# Sensor.net
KiCad netlist of a schematic drawn in Altium Designer
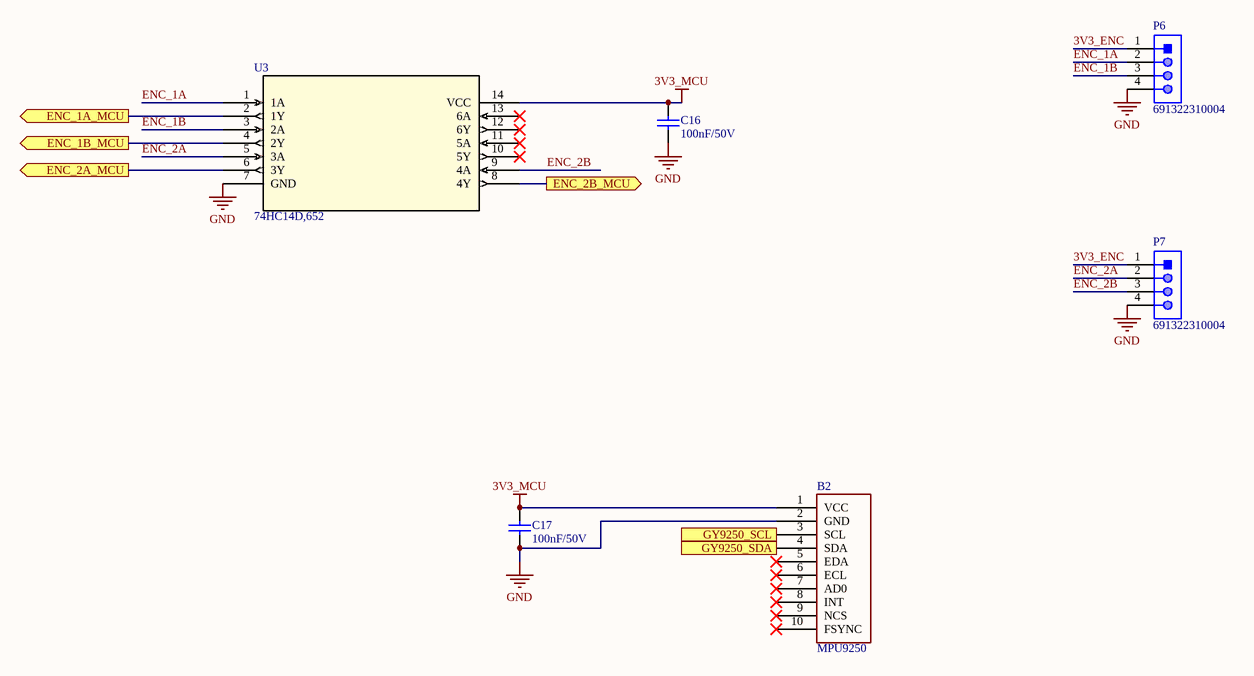
[diagram p0: Sensor.SchDoc]

(export (version "E")
  (design (tool "Eeschema 10.0.6"))
  (components
    (comp (ref "B2") (value "MPU9250") (footprint "MPU9250") (libsource (lib "Board") (part "MPU9250")))
    (comp (ref "C16")
      (value "100nF/50V")
      (footprint "CAP-SM-0805")
      (description "CAP CER 0.1UF 50V Y5V 0805")
      (fields
        (field (name "MANUFACTURER") "Samsung Electro-Mechanics")
        (field (name "MANUFACTURER PART NUMBER") "CL21F104ZBCNNNC")
      )
      (libsource (lib "Capacitor") (part "Cap-100nF-50V-0805"))
    )
    (comp (ref "C17")
      (value "100nF/50V")
      (footprint "CAP-SM-0805")
      (description "CAP CER 0.1UF 50V Y5V 0805")
      (fields
        (field (name "MANUFACTURER") "Samsung Electro-Mechanics")
        (field (name "MANUFACTURER PART NUMBER") "CL21F104ZBCNNNC")
      )
      (libsource (lib "Capacitor") (part "Cap-100nF-50V-0805"))
    )
    (comp (ref "P6")
      (value "691322310004")
      (footprint "Project_Xe_Can_Bang:691322310004")
      (description "WR-TBL Serie 322 Horizontal PCB Header, Pluggable, pitch 3.81mm, 4p")
      (fields (field (name "PUBLISHER") "Wurth Elektronik"))
      (libsource (lib "Project_Xe_Can_Bang") (part "691322310004"))
    )
    (comp (ref "P7")
      (value "691322310004")
      (footprint "Project_Xe_Can_Bang:691322310004")
      (description "WR-TBL Serie 322 Horizontal PCB Header, Pluggable, pitch 3.81mm, 4p")
      (fields (field (name "PUBLISHER") "Wurth Elektronik"))
      (libsource (lib "Project_Xe_Can_Bang") (part "691322310004"))
    )
    (comp (ref "U3")
      (value "74HC14D,652")
      (footprint "SOT108-1_NEX")
      (description "No Description Available")
      (fields (field (name "COPYRIGHT") "Copyright (C) 2016 Accelerated Designs. All rights reserved"))
      (libsource (lib "74HC14D_625_2020-06-19_15-46-23") (part "74HC14D,652"))
    )
  )
  (nets
    (net (code "1") (name "/3V3_ENC") (class "Default")
      (node (ref "P6") (pin "1") (pinfunction "1_1") (pintype "passive"))
      (node (ref "P7") (pin "1") (pinfunction "1_1") (pintype "passive"))
    )
    (net (code "2") (name "/ENC_1A") (class "Default")
      (node (ref "P6") (pin "2") (pinfunction "2_2") (pintype "passive"))
      (node (ref "U3") (pin "1") (pinfunction "1A_1") (pintype "input"))
    )
    (net (code "3") (name "/ENC_1A_MCU") (class "Default")
      (node (ref "U3") (pin "2") (pinfunction "1Y_2") (pintype "output"))
    )
    (net (code "4") (name "/ENC_1B") (class "Default")
      (node (ref "P6") (pin "3") (pinfunction "3_3") (pintype "passive"))
      (node (ref "U3") (pin "3") (pinfunction "2A_3") (pintype "input"))
    )
    (net (code "5") (name "/ENC_1B_MCU") (class "Default")
      (node (ref "U3") (pin "4") (pinfunction "2Y_4") (pintype "output"))
    )
    (net (code "6") (name "/ENC_2A") (class "Default")
      (node (ref "P7") (pin "2") (pinfunction "2_2") (pintype "passive"))
      (node (ref "U3") (pin "5") (pinfunction "3A_5") (pintype "input"))
    )
    (net (code "7") (name "/ENC_2A_MCU") (class "Default")
      (node (ref "U3") (pin "6") (pinfunction "3Y_6") (pintype "output"))
    )
    (net (code "8") (name "/ENC_2B") (class "Default")
      (node (ref "P7") (pin "3") (pinfunction "3_3") (pintype "passive"))
      (node (ref "U3") (pin "9") (pinfunction "4A_9") (pintype "input"))
    )
    (net (code "9") (name "/ENC_2B_MCU") (class "Default")
      (node (ref "U3") (pin "8") (pinfunction "4Y_8") (pintype "output"))
    )
    (net (code "10") (name "/GY9250_SCL") (class "Default")
      (node (ref "B2") (pin "3") (pinfunction "SCL_3") (pintype "passive"))
    )
    (net (code "11") (name "/GY9250_SDA") (class "Default")
      (node (ref "B2") (pin "4") (pinfunction "SDA_4") (pintype "passive"))
    )
    (net (code "12") (name "3V3_MCU") (class "Default")
      (node (ref "B2") (pin "1") (pinfunction "VCC_1") (pintype "passive"))
      (node (ref "C16") (pin "2") (pinfunction "2_2") (pintype "passive"))
      (node (ref "C17") (pin "2") (pinfunction "2_2") (pintype "passive"))
      (node (ref "U3") (pin "14") (pinfunction "VCC_14") (pintype "power_in"))
    )
    (net (code "13") (name "GND") (class "Default")
      (node (ref "B2") (pin "2") (pinfunction "GND_2") (pintype "passive"))
      (node (ref "C16") (pin "1") (pinfunction "1_1") (pintype "passive"))
      (node (ref "C17") (pin "1") (pinfunction "1_1") (pintype "passive"))
      (node (ref "P6") (pin "4") (pinfunction "4_4") (pintype "passive"))
      (node (ref "P7") (pin "4") (pinfunction "4_4") (pintype "passive"))
      (node (ref "U3") (pin "7") (pinfunction "GND_7") (pintype "power_in"))
    )
    (net (code "14") (name "unconnected-(B2-AD0-Pad7)") (class "Default")
      (node (ref "B2") (pin "7") (pinfunction "AD0_7") (pintype "passive+no_connect"))
    )
    (net (code "15") (name "unconnected-(B2-ECL-Pad6)") (class "Default")
      (node (ref "B2") (pin "6") (pinfunction "ECL_6") (pintype "passive+no_connect"))
    )
    (net (code "16") (name "unconnected-(B2-EDA-Pad5)") (class "Default")
      (node (ref "B2") (pin "5") (pinfunction "EDA_5") (pintype "passive+no_connect"))
    )
    (net (code "17") (name "unconnected-(B2-FSYNC-Pad10)") (class "Default")
      (node (ref "B2") (pin "10") (pinfunction "FSYNC_10") (pintype "passive+no_connect"))
    )
    (net (code "18") (name "unconnected-(B2-INT-Pad8)") (class "Default")
      (node (ref "B2") (pin "8") (pinfunction "INT_8") (pintype "passive+no_connect"))
    )
    (net (code "19") (name "unconnected-(B2-NCS-Pad9)") (class "Default")
      (node (ref "B2") (pin "9") (pinfunction "NCS_9") (pintype "passive+no_connect"))
    )
    (net (code "20") (name "unconnected-(U3-5A-Pad11)") (class "Default")
      (node (ref "U3") (pin "11") (pinfunction "5A_11") (pintype "input+no_connect"))
    )
    (net (code "21") (name "unconnected-(U3-5Y-Pad10)") (class "Default")
      (node (ref "U3") (pin "10") (pinfunction "5Y_10") (pintype "output+no_connect"))
    )
    (net (code "22") (name "unconnected-(U3-6A-Pad13)") (class "Default")
      (node (ref "U3") (pin "13") (pinfunction "6A_13") (pintype "input+no_connect"))
    )
    (net (code "23") (name "unconnected-(U3-6Y-Pad12)") (class "Default")
      (node (ref "U3") (pin "12") (pinfunction "6Y_12") (pintype "output+no_connect"))
    )
  )
)
